# two_ant_fpga_board.net
KiCad netlist of a schematic drawn in Altium Designer
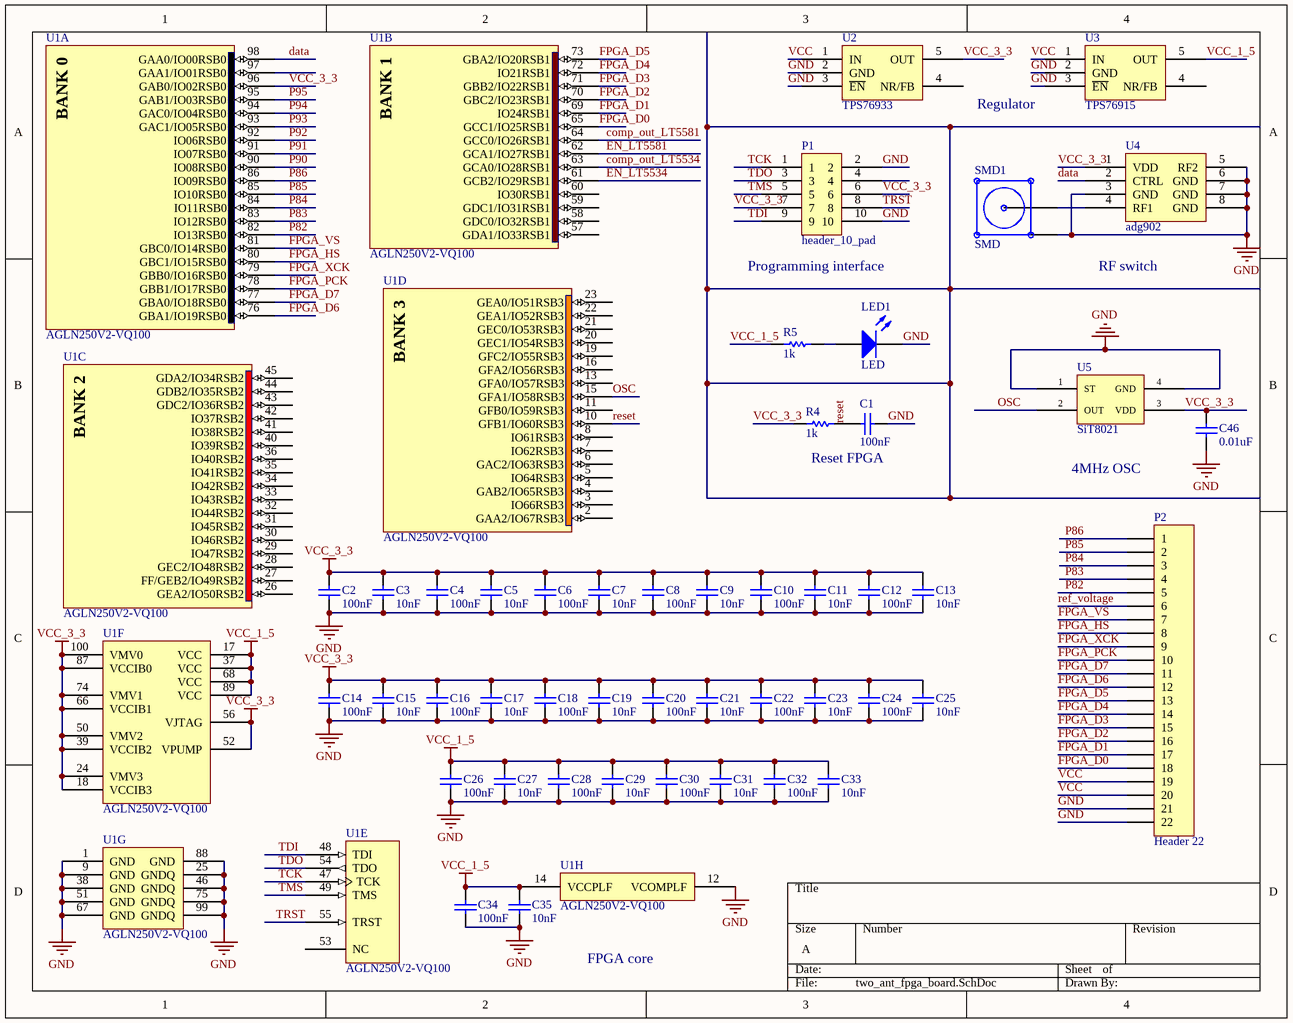
[diagram p0: two_ant_fpga_board.SchDoc]

(export (version "E")
  (design (tool "Eeschema 10.0.6"))
  (components
    (comp (ref "C1")
      (value "100nF")
      (footprint "0603")
      (description "Ceramic Capacitor (Surface Mount)")
      (fields (field (name "MANUFACTURER") "Generic Ceramic Chip Cap (TBD)") (field (name "Comment") "Cap"))
      (libsource (lib "wisp") (part "Cap"))
    )
    (comp (ref "C2")
      (value "100nF")
      (footprint "0603")
      (description "Ceramic Capacitor (Surface Mount)")
      (fields (field (name "MANUFACTURER") "Generic Ceramic Chip Cap (TBD)") (field (name "Comment") "Cap"))
      (libsource (lib "wisp") (part "Cap"))
    )
    (comp (ref "C3")
      (value "10nF")
      (footprint "0603")
      (description "Ceramic Capacitor (Surface Mount)")
      (fields (field (name "MANUFACTURER") "Generic Ceramic Chip Cap (TBD)") (field (name "Comment") "Cap"))
      (libsource (lib "wisp") (part "Cap"))
    )
    (comp (ref "C4")
      (value "100nF")
      (footprint "0603")
      (description "Ceramic Capacitor (Surface Mount)")
      (fields (field (name "MANUFACTURER") "Generic Ceramic Chip Cap (TBD)") (field (name "Comment") "Cap"))
      (libsource (lib "wisp") (part "Cap"))
    )
    (comp (ref "C5")
      (value "10nF")
      (footprint "0603")
      (description "Ceramic Capacitor (Surface Mount)")
      (fields (field (name "MANUFACTURER") "Generic Ceramic Chip Cap (TBD)") (field (name "Comment") "Cap"))
      (libsource (lib "wisp") (part "Cap"))
    )
    (comp (ref "C6")
      (value "100nF")
      (footprint "0603")
      (description "Ceramic Capacitor (Surface Mount)")
      (fields (field (name "MANUFACTURER") "Generic Ceramic Chip Cap (TBD)") (field (name "Comment") "Cap"))
      (libsource (lib "wisp") (part "Cap"))
    )
    (comp (ref "C7")
      (value "10nF")
      (footprint "0603")
      (description "Ceramic Capacitor (Surface Mount)")
      (fields (field (name "MANUFACTURER") "Generic Ceramic Chip Cap (TBD)") (field (name "Comment") "Cap"))
      (libsource (lib "wisp") (part "Cap"))
    )
    (comp (ref "C8")
      (value "100nF")
      (footprint "0603")
      (description "Ceramic Capacitor (Surface Mount)")
      (fields (field (name "MANUFACTURER") "Generic Ceramic Chip Cap (TBD)") (field (name "Comment") "Cap"))
      (libsource (lib "wisp") (part "Cap"))
    )
    (comp (ref "C9")
      (value "10nF")
      (footprint "0603")
      (description "Ceramic Capacitor (Surface Mount)")
      (fields (field (name "MANUFACTURER") "Generic Ceramic Chip Cap (TBD)") (field (name "Comment") "Cap"))
      (libsource (lib "wisp") (part "Cap"))
    )
    (comp (ref "C10")
      (value "100nF")
      (footprint "0603")
      (description "Ceramic Capacitor (Surface Mount)")
      (fields (field (name "MANUFACTURER") "Generic Ceramic Chip Cap (TBD)") (field (name "Comment") "Cap"))
      (libsource (lib "wisp") (part "Cap"))
    )
    (comp (ref "C11")
      (value "10nF")
      (footprint "0603")
      (description "Ceramic Capacitor (Surface Mount)")
      (fields (field (name "MANUFACTURER") "Generic Ceramic Chip Cap (TBD)") (field (name "Comment") "Cap"))
      (libsource (lib "wisp") (part "Cap"))
    )
    (comp (ref "C12")
      (value "100nF")
      (footprint "0603")
      (description "Ceramic Capacitor (Surface Mount)")
      (fields (field (name "MANUFACTURER") "Generic Ceramic Chip Cap (TBD)") (field (name "Comment") "Cap"))
      (libsource (lib "wisp") (part "Cap"))
    )
    (comp (ref "C13")
      (value "10nF")
      (footprint "0603")
      (description "Ceramic Capacitor (Surface Mount)")
      (fields (field (name "MANUFACTURER") "Generic Ceramic Chip Cap (TBD)") (field (name "Comment") "Cap"))
      (libsource (lib "wisp") (part "Cap"))
    )
    (comp (ref "C14")
      (value "100nF")
      (footprint "0603")
      (description "Ceramic Capacitor (Surface Mount)")
      (fields (field (name "MANUFACTURER") "Generic Ceramic Chip Cap (TBD)") (field (name "Comment") "Cap"))
      (libsource (lib "wisp") (part "Cap"))
    )
    (comp (ref "C15")
      (value "10nF")
      (footprint "0603")
      (description "Ceramic Capacitor (Surface Mount)")
      (fields (field (name "MANUFACTURER") "Generic Ceramic Chip Cap (TBD)") (field (name "Comment") "Cap"))
      (libsource (lib "wisp") (part "Cap"))
    )
    (comp (ref "C16")
      (value "100nF")
      (footprint "0603")
      (description "Ceramic Capacitor (Surface Mount)")
      (fields (field (name "MANUFACTURER") "Generic Ceramic Chip Cap (TBD)") (field (name "Comment") "Cap"))
      (libsource (lib "wisp") (part "Cap"))
    )
    (comp (ref "C17")
      (value "10nF")
      (footprint "0603")
      (description "Ceramic Capacitor (Surface Mount)")
      (fields (field (name "MANUFACTURER") "Generic Ceramic Chip Cap (TBD)") (field (name "Comment") "Cap"))
      (libsource (lib "wisp") (part "Cap"))
    )
    (comp (ref "C18")
      (value "100nF")
      (footprint "0603")
      (description "Ceramic Capacitor (Surface Mount)")
      (fields (field (name "MANUFACTURER") "Generic Ceramic Chip Cap (TBD)") (field (name "Comment") "Cap"))
      (libsource (lib "wisp") (part "Cap"))
    )
    (comp (ref "C19")
      (value "10nF")
      (footprint "0603")
      (description "Ceramic Capacitor (Surface Mount)")
      (fields (field (name "MANUFACTURER") "Generic Ceramic Chip Cap (TBD)") (field (name "Comment") "Cap"))
      (libsource (lib "wisp") (part "Cap"))
    )
    (comp (ref "C20")
      (value "100nF")
      (footprint "0603")
      (description "Ceramic Capacitor (Surface Mount)")
      (fields (field (name "MANUFACTURER") "Generic Ceramic Chip Cap (TBD)") (field (name "Comment") "Cap"))
      (libsource (lib "wisp") (part "Cap"))
    )
    (comp (ref "C21")
      (value "10nF")
      (footprint "0603")
      (description "Ceramic Capacitor (Surface Mount)")
      (fields (field (name "MANUFACTURER") "Generic Ceramic Chip Cap (TBD)") (field (name "Comment") "Cap"))
      (libsource (lib "wisp") (part "Cap"))
    )
    (comp (ref "C22")
      (value "100nF")
      (footprint "0603")
      (description "Ceramic Capacitor (Surface Mount)")
      (fields (field (name "MANUFACTURER") "Generic Ceramic Chip Cap (TBD)") (field (name "Comment") "Cap"))
      (libsource (lib "wisp") (part "Cap"))
    )
    (comp (ref "C23")
      (value "10nF")
      (footprint "0603")
      (description "Ceramic Capacitor (Surface Mount)")
      (fields (field (name "MANUFACTURER") "Generic Ceramic Chip Cap (TBD)") (field (name "Comment") "Cap"))
      (libsource (lib "wisp") (part "Cap"))
    )
    (comp (ref "C24")
      (value "100nF")
      (footprint "0603")
      (description "Ceramic Capacitor (Surface Mount)")
      (fields (field (name "MANUFACTURER") "Generic Ceramic Chip Cap (TBD)") (field (name "Comment") "Cap"))
      (libsource (lib "wisp") (part "Cap"))
    )
    (comp (ref "C25")
      (value "10nF")
      (footprint "0603")
      (description "Ceramic Capacitor (Surface Mount)")
      (fields (field (name "MANUFACTURER") "Generic Ceramic Chip Cap (TBD)") (field (name "Comment") "Cap"))
      (libsource (lib "wisp") (part "Cap"))
    )
    (comp (ref "C26")
      (value "100nF")
      (footprint "0603")
      (description "Ceramic Capacitor (Surface Mount)")
      (fields (field (name "MANUFACTURER") "Generic Ceramic Chip Cap (TBD)") (field (name "Comment") "Cap"))
      (libsource (lib "wisp") (part "Cap"))
    )
    (comp (ref "C27")
      (value "10nF")
      (footprint "0603")
      (description "Ceramic Capacitor (Surface Mount)")
      (fields (field (name "MANUFACTURER") "Generic Ceramic Chip Cap (TBD)") (field (name "Comment") "Cap"))
      (libsource (lib "wisp") (part "Cap"))
    )
    (comp (ref "C28")
      (value "100nF")
      (footprint "0603")
      (description "Ceramic Capacitor (Surface Mount)")
      (fields (field (name "MANUFACTURER") "Generic Ceramic Chip Cap (TBD)") (field (name "Comment") "Cap"))
      (libsource (lib "wisp") (part "Cap"))
    )
    (comp (ref "C29")
      (value "10nF")
      (footprint "0603")
      (description "Ceramic Capacitor (Surface Mount)")
      (fields (field (name "MANUFACTURER") "Generic Ceramic Chip Cap (TBD)") (field (name "Comment") "Cap"))
      (libsource (lib "wisp") (part "Cap"))
    )
    (comp (ref "C30")
      (value "100nF")
      (footprint "0603")
      (description "Ceramic Capacitor (Surface Mount)")
      (fields (field (name "MANUFACTURER") "Generic Ceramic Chip Cap (TBD)") (field (name "Comment") "Cap"))
      (libsource (lib "wisp") (part "Cap"))
    )
    (comp (ref "C31")
      (value "10nF")
      (footprint "0603")
      (description "Ceramic Capacitor (Surface Mount)")
      (fields (field (name "MANUFACTURER") "Generic Ceramic Chip Cap (TBD)") (field (name "Comment") "Cap"))
      (libsource (lib "wisp") (part "Cap"))
    )
    (comp (ref "C32")
      (value "100nF")
      (footprint "0603")
      (description "Ceramic Capacitor (Surface Mount)")
      (fields (field (name "MANUFACTURER") "Generic Ceramic Chip Cap (TBD)") (field (name "Comment") "Cap"))
      (libsource (lib "wisp") (part "Cap"))
    )
    (comp (ref "C33")
      (value "10nF")
      (footprint "0603")
      (description "Ceramic Capacitor (Surface Mount)")
      (fields (field (name "MANUFACTURER") "Generic Ceramic Chip Cap (TBD)") (field (name "Comment") "Cap"))
      (libsource (lib "wisp") (part "Cap"))
    )
    (comp (ref "C34")
      (value "100nF")
      (footprint "0603")
      (description "Ceramic Capacitor (Surface Mount)")
      (fields (field (name "MANUFACTURER") "Generic Ceramic Chip Cap (TBD)") (field (name "Comment") "Cap"))
      (libsource (lib "wisp") (part "Cap"))
    )
    (comp (ref "C35")
      (value "10nF")
      (footprint "0603")
      (description "Ceramic Capacitor (Surface Mount)")
      (fields (field (name "MANUFACTURER") "Generic Ceramic Chip Cap (TBD)") (field (name "Comment") "Cap"))
      (libsource (lib "wisp") (part "Cap"))
    )
    (comp (ref "C46")
      (value "0.01uF")
      (footprint "0603")
      (description "Ceramic Capacitor (Surface Mount)")
      (fields (field (name "MANUFACTURER") "Generic Ceramic Chip Cap (TBD)") (field (name "Comment") "Cap"))
      (libsource (lib "wisp") (part "Cap"))
    )
    (comp (ref "LED1") (value "LED") (libsource (lib "pengyulib") (part "LED")))
    (comp (ref "P1")
      (value "header_10_pad")
      (footprint "header_10_pad")
      (libsource (lib "pengyulib") (part "header_10_pad"))
    )
    (comp (ref "P2")
      (value "Header 22")
      (footprint "HDR1X22")
      (description "Header, 22-Pin")
      (fields (field (name "PUBLISHER") "Altium Limited"))
      (libsource (lib "Miscellaneous Connectors") (part "Header 22"))
    )
    (comp (ref "R4")
      (value "1k")
      (footprint "0603")
      (description "Chip Resistor (Surface Mount)")
      (fields (field (name "MANUFACTURER") "Generic Chip Res (TBD)") (field (name "Comment") "Res"))
      (libsource (lib "wisp") (part "Res"))
    )
    (comp (ref "R5")
      (value "1k")
      (footprint "0603")
      (description "Chip Resistor (Surface Mount)")
      (fields (field (name "MANUFACTURER") "Generic Chip Res (TBD)") (field (name "Comment") "Res"))
      (libsource (lib "wisp") (part "Res"))
    )
    (comp (ref "SMD1") (value "SMD") (footprint "SMD") (libsource (lib "pengyulib") (part "SMD")))
    (comp (ref "U1")
      (value "AGLN250V2-VQ100")
      (footprint "VQ100_N")
      (fields (field (name "PUBLISHER") "Altium Limited"))
      (libsource (lib "Actel IGLOO nano") (part "AGLN250V2-VQ100"))
    )
    (comp (ref "U2")
      (value "TPS76933")
      (footprint "TPS73633")
      (description "TPS73633")
      (libsource (lib "pengyulib") (part "TPS76933"))
    )
    (comp (ref "U3")
      (value "TPS76915")
      (footprint "TPS73633")
      (description "TPS73633")
      (libsource (lib "pengyulib") (part "TPS76915"))
    )
    (comp (ref "U4") (value "adg902") (footprint "ADG902") (libsource (lib "pengyulib") (part "adg902")))
    (comp (ref "U5") (value "SiT8021") (footprint "SiT8021") (libsource (lib "pengyulib") (part "SiT8021")))
  )
  (nets
    (net (code "1") (name "/EN_LT5534") (class "Default")
      (node (ref "U1") (pin "61") (pinfunction "GCB2/IO29RSB1_61") (pintype "bidirectional"))
    )
    (net (code "2") (name "/EN_LT5581") (class "Default")
      (node (ref "U1") (pin "62") (pinfunction "GCA1/IO27RSB1_62") (pintype "bidirectional"))
    )
    (net (code "3") (name "/FPGA_D0") (class "Default")
      (node (ref "P2") (pin "18") (pinfunction "18_18") (pintype "passive"))
      (node (ref "U1") (pin "65") (pinfunction "GCC1/IO25RSB1_65") (pintype "bidirectional"))
    )
    (net (code "4") (name "/FPGA_D1") (class "Default")
      (node (ref "P2") (pin "17") (pinfunction "17_17") (pintype "passive"))
      (node (ref "U1") (pin "69") (pinfunction "IO24RSB1_69") (pintype "bidirectional"))
    )
    (net (code "5") (name "/FPGA_D2") (class "Default")
      (node (ref "P2") (pin "16") (pinfunction "16_16") (pintype "passive"))
      (node (ref "U1") (pin "70") (pinfunction "GBC2/IO23RSB1_70") (pintype "bidirectional"))
    )
    (net (code "6") (name "/FPGA_D3") (class "Default")
      (node (ref "P2") (pin "15") (pinfunction "15_15") (pintype "passive"))
      (node (ref "U1") (pin "71") (pinfunction "GBB2/IO22RSB1_71") (pintype "bidirectional"))
    )
    (net (code "7") (name "/FPGA_D4") (class "Default")
      (node (ref "P2") (pin "14") (pinfunction "14_14") (pintype "passive"))
      (node (ref "U1") (pin "72") (pinfunction "IO21RSB1_72") (pintype "bidirectional"))
    )
    (net (code "8") (name "/FPGA_D5") (class "Default")
      (node (ref "P2") (pin "13") (pinfunction "13_13") (pintype "passive"))
      (node (ref "U1") (pin "73") (pinfunction "GBA2/IO20RSB1_73") (pintype "bidirectional"))
    )
    (net (code "9") (name "/FPGA_D6") (class "Default")
      (node (ref "P2") (pin "12") (pinfunction "12_12") (pintype "passive"))
      (node (ref "U1") (pin "76") (pinfunction "GBA1/IO19RSB0_76") (pintype "bidirectional"))
    )
    (net (code "10") (name "/FPGA_D7") (class "Default")
      (node (ref "P2") (pin "11") (pinfunction "11_11") (pintype "passive"))
      (node (ref "U1") (pin "77") (pinfunction "GBA0/IO18RSB0_77") (pintype "bidirectional"))
    )
    (net (code "11") (name "/FPGA_HS") (class "Default")
      (node (ref "P2") (pin "8") (pinfunction "8_8") (pintype "passive"))
      (node (ref "U1") (pin "80") (pinfunction "GBC1/IO15RSB0_80") (pintype "bidirectional"))
    )
    (net (code "12") (name "/FPGA_PCK") (class "Default")
      (node (ref "P2") (pin "10") (pinfunction "10_10") (pintype "passive"))
      (node (ref "U1") (pin "78") (pinfunction "GBB1/IO17RSB0_78") (pintype "bidirectional"))
    )
    (net (code "13") (name "/FPGA_VS") (class "Default")
      (node (ref "P2") (pin "7") (pinfunction "7_7") (pintype "passive"))
      (node (ref "U1") (pin "81") (pinfunction "GBC0/IO14RSB0_81") (pintype "bidirectional"))
    )
    (net (code "14") (name "/FPGA_XCK") (class "Default")
      (node (ref "P2") (pin "9") (pinfunction "9_9") (pintype "passive"))
      (node (ref "U1") (pin "79") (pinfunction "GBB0/IO16RSB0_79") (pintype "bidirectional"))
    )
    (net (code "15") (name "/OSC") (class "Default")
      (node (ref "U1") (pin "15") (pinfunction "GFA1/IO58RSB3_15") (pintype "bidirectional"))
      (node (ref "U5") (pin "2") (pinfunction "OUT_2") (pintype "passive"))
    )
    (net (code "16") (name "/P82") (class "Default")
      (node (ref "P2") (pin "5") (pinfunction "5_5") (pintype "passive"))
      (node (ref "U1") (pin "82") (pinfunction "IO13RSB0_82") (pintype "bidirectional"))
    )
    (net (code "17") (name "/P83") (class "Default")
      (node (ref "P2") (pin "4") (pinfunction "4_4") (pintype "passive"))
      (node (ref "U1") (pin "83") (pinfunction "IO12RSB0_83") (pintype "bidirectional"))
    )
    (net (code "18") (name "/P84") (class "Default")
      (node (ref "P2") (pin "3") (pinfunction "3_3") (pintype "passive"))
      (node (ref "U1") (pin "84") (pinfunction "IO11RSB0_84") (pintype "bidirectional"))
    )
    (net (code "19") (name "/P85") (class "Default")
      (node (ref "P2") (pin "2") (pinfunction "2_2") (pintype "passive"))
      (node (ref "U1") (pin "85") (pinfunction "IO10RSB0_85") (pintype "bidirectional"))
    )
    (net (code "20") (name "/P86") (class "Default")
      (node (ref "P2") (pin "1") (pinfunction "1_1") (pintype "passive"))
      (node (ref "U1") (pin "86") (pinfunction "IO09RSB0_86") (pintype "bidirectional"))
    )
    (net (code "21") (name "/P90") (class "Default")
      (node (ref "U1") (pin "90") (pinfunction "IO08RSB0_90") (pintype "bidirectional"))
    )
    (net (code "22") (name "/P91") (class "Default")
      (node (ref "U1") (pin "91") (pinfunction "IO07RSB0_91") (pintype "bidirectional"))
    )
    (net (code "23") (name "/P92") (class "Default")
      (node (ref "U1") (pin "92") (pinfunction "IO06RSB0_92") (pintype "bidirectional"))
    )
    (net (code "24") (name "/P93") (class "Default")
      (node (ref "U1") (pin "93") (pinfunction "GAC1/IO05RSB0_93") (pintype "bidirectional"))
    )
    (net (code "25") (name "/P94") (class "Default")
      (node (ref "U1") (pin "94") (pinfunction "GAC0/IO04RSB0_94") (pintype "bidirectional"))
    )
    (net (code "26") (name "/P95") (class "Default")
      (node (ref "U1") (pin "95") (pinfunction "GAB1/IO03RSB0_95") (pintype "bidirectional"))
    )
    (net (code "27") (name "/TCK") (class "Default")
      (node (ref "P1") (pin "1") (pinfunction "1_1") (pintype "passive"))
      (node (ref "U1") (pin "47") (pinfunction "TCK_47") (pintype "input"))
    )
    (net (code "28") (name "/TDI") (class "Default")
      (node (ref "P1") (pin "9") (pinfunction "9_9") (pintype "passive"))
      (node (ref "U1") (pin "48") (pinfunction "TDI_48") (pintype "input"))
    )
    (net (code "29") (name "/TDO") (class "Default")
      (node (ref "P1") (pin "3") (pinfunction "3_3") (pintype "passive"))
      (node (ref "U1") (pin "54") (pinfunction "TDO_54") (pintype "output"))
    )
    (net (code "30") (name "/TMS") (class "Default")
      (node (ref "P1") (pin "5") (pinfunction "5_5") (pintype "passive"))
      (node (ref "U1") (pin "49") (pinfunction "TMS_49") (pintype "input"))
    )
    (net (code "31") (name "/TRST") (class "Default")
      (node (ref "P1") (pin "8") (pinfunction "8_8") (pintype "passive"))
      (node (ref "U1") (pin "55") (pinfunction "TRST_55") (pintype "input"))
    )
    (net (code "32") (name "/VCC") (class "Default")
      (node (ref "P2") (pin "19") (pinfunction "19_19") (pintype "passive"))
      (node (ref "P2") (pin "20") (pinfunction "20_20") (pintype "passive"))
      (node (ref "U2") (pin "1") (pinfunction "IN_1") (pintype "passive"))
      (node (ref "U3") (pin "1") (pinfunction "IN_1") (pintype "passive"))
    )
    (net (code "33") (name "/comp_out_LT5534") (class "Default")
      (node (ref "U1") (pin "63") (pinfunction "GCA0/IO28RSB1_63") (pintype "bidirectional"))
    )
    (net (code "34") (name "/comp_out_LT5581") (class "Default")
      (node (ref "U1") (pin "64") (pinfunction "GCC0/IO26RSB1_64") (pintype "bidirectional"))
    )
    (net (code "35") (name "/data") (class "Default")
      (node (ref "U1") (pin "98") (pinfunction "GAA0/IO00RSB0_98") (pintype "bidirectional"))
      (node (ref "U4") (pin "2") (pinfunction "CTRL_2") (pintype "passive"))
    )
    (net (code "36") (name "/ref_voltage") (class "Default")
      (node (ref "P2") (pin "6") (pinfunction "6_6") (pintype "passive"))
    )
    (net (code "37") (name "/reset") (class "Default")
      (node (ref "C1") (pin "2") (pinfunction "2_2") (pintype "passive"))
      (node (ref "R4") (pin "1") (pinfunction "1_1") (pintype "passive"))
      (node (ref "U1") (pin "10") (pinfunction "GFB1/IO60RSB3_10") (pintype "bidirectional"))
    )
    (net (code "38") (name "GND") (class "Default")
      (node (ref "C1") (pin "1") (pinfunction "1_1") (pintype "passive"))
      (node (ref "C10") (pin "1") (pinfunction "1_1") (pintype "passive"))
      (node (ref "C11") (pin "1") (pinfunction "1_1") (pintype "passive"))
      (node (ref "C12") (pin "1") (pinfunction "1_1") (pintype "passive"))
      (node (ref "C13") (pin "1") (pinfunction "1_1") (pintype "passive"))
      (node (ref "C14") (pin "1") (pinfunction "1_1") (pintype "passive"))
      (node (ref "C15") (pin "1") (pinfunction "1_1") (pintype "passive"))
      (node (ref "C16") (pin "1") (pinfunction "1_1") (pintype "passive"))
      (node (ref "C17") (pin "1") (pinfunction "1_1") (pintype "passive"))
      (node (ref "C18") (pin "1") (pinfunction "1_1") (pintype "passive"))
      (node (ref "C19") (pin "1") (pinfunction "1_1") (pintype "passive"))
      (node (ref "C2") (pin "1") (pinfunction "1_1") (pintype "passive"))
      (node (ref "C20") (pin "1") (pinfunction "1_1") (pintype "passive"))
      (node (ref "C21") (pin "1") (pinfunction "1_1") (pintype "passive"))
      (node (ref "C22") (pin "1") (pinfunction "1_1") (pintype "passive"))
      (node (ref "C23") (pin "1") (pinfunction "1_1") (pintype "passive"))
      (node (ref "C24") (pin "1") (pinfunction "1_1") (pintype "passive"))
      (node (ref "C25") (pin "1") (pinfunction "1_1") (pintype "passive"))
      (node (ref "C26") (pin "1") (pinfunction "1_1") (pintype "passive"))
      (node (ref "C27") (pin "1") (pinfunction "1_1") (pintype "passive"))
      (node (ref "C28") (pin "1") (pinfunction "1_1") (pintype "passive"))
      (node (ref "C29") (pin "1") (pinfunction "1_1") (pintype "passive"))
      (node (ref "C3") (pin "1") (pinfunction "1_1") (pintype "passive"))
      (node (ref "C30") (pin "1") (pinfunction "1_1") (pintype "passive"))
      (node (ref "C31") (pin "1") (pinfunction "1_1") (pintype "passive"))
      (node (ref "C32") (pin "1") (pinfunction "1_1") (pintype "passive"))
      (node (ref "C33") (pin "1") (pinfunction "1_1") (pintype "passive"))
      (node (ref "C34") (pin "1") (pinfunction "1_1") (pintype "passive"))
      (node (ref "C35") (pin "1") (pinfunction "1_1") (pintype "passive"))
      (node (ref "C4") (pin "1") (pinfunction "1_1") (pintype "passive"))
      (node (ref "C46") (pin "1") (pinfunction "1_1") (pintype "passive"))
      (node (ref "C5") (pin "1") (pinfunction "1_1") (pintype "passive"))
      (node (ref "C6") (pin "1") (pinfunction "1_1") (pintype "passive"))
      (node (ref "C7") (pin "1") (pinfunction "1_1") (pintype "passive"))
      (node (ref "C8") (pin "1") (pinfunction "1_1") (pintype "passive"))
      (node (ref "C9") (pin "1") (pinfunction "1_1") (pintype "passive"))
      (node (ref "LED1") (pin "2") (pinfunction "K_2") (pintype "passive"))
      (node (ref "P1") (pin "10") (pinfunction "10_10") (pintype "passive"))
      (node (ref "P1") (pin "2") (pinfunction "2_2") (pintype "passive"))
      (node (ref "P2") (pin "21") (pinfunction "21_21") (pintype "passive"))
      (node (ref "P2") (pin "22") (pinfunction "22_22") (pintype "passive"))
      (node (ref "SMD1") (pin "1") (pinfunction "1_1") (pintype "passive"))
      (node (ref "U1") (pin "1") (pinfunction "GND_1") (pintype "power_in"))
      (node (ref "U1") (pin "12") (pinfunction "VCOMPLF_12") (pintype "power_in"))
      (node (ref "U1") (pin "25") (pinfunction "GNDQ_25") (pintype "power_in"))
      (node (ref "U1") (pin "38") (pinfunction "GND_38") (pintype "power_in"))
      (node (ref "U1") (pin "46") (pinfunction "GNDQ_46") (pintype "power_in"))
      (node (ref "U1") (pin "51") (pinfunction "GND_51") (pintype "power_in"))
      (node (ref "U1") (pin "67") (pinfunction "GND_67") (pintype "power_in"))
      (node (ref "U1") (pin "75") (pinfunction "GNDQ_75") (pintype "power_in"))
      (node (ref "U1") (pin "88") (pinfunction "GND_88") (pintype "power_in"))
      (node (ref "U1") (pin "9") (pinfunction "GND_9") (pintype "power_in"))
      (node (ref "U1") (pin "99") (pinfunction "GNDQ_99") (pintype "power_in"))
      (node (ref "U2") (pin "2") (pinfunction "GND_2") (pintype "passive"))
      (node (ref "U2") (pin "3") (pinfunction "~{EN}_3") (pintype "passive"))
      (node (ref "U3") (pin "2") (pinfunction "GND_2") (pintype "passive"))
      (node (ref "U3") (pin "3") (pinfunction "~{EN}_3") (pintype "passive"))
      (node (ref "U4") (pin "3") (pinfunction "GND_3") (pintype "passive"))
      (node (ref "U4") (pin "5") (pinfunction "RF2_5") (pintype "passive"))
      (node (ref "U4") (pin "6") (pinfunction "GND_6") (pintype "passive"))
      (node (ref "U4") (pin "7") (pinfunction "GND_7") (pintype "passive"))
      (node (ref "U4") (pin "8") (pinfunction "GND_8") (pintype "passive"))
      (node (ref "U5") (pin "1") (pinfunction "ST_1") (pintype "passive"))
      (node (ref "U5") (pin "4") (pinfunction "GND_4") (pintype "passive"))
    )
    (net (code "39") (name "Net-(LED1-A)") (class "Default")
      (node (ref "LED1") (pin "1") (pinfunction "A_1") (pintype "passive"))
      (node (ref "R5") (pin "1") (pinfunction "1_1") (pintype "passive"))
    )
    (net (code "40") (name "Net-(U4-RF1)") (class "Default")
      (node (ref "SMD1") (pin "2") (pinfunction "2_2") (pintype "passive"))
      (node (ref "U4") (pin "4") (pinfunction "RF1_4") (pintype "passive"))
    )
    (net (code "41") (name "VCC_1_5") (class "Default")
      (node (ref "C26") (pin "2") (pinfunction "2_2") (pintype "passive"))
      (node (ref "C27") (pin "2") (pinfunction "2_2") (pintype "passive"))
      (node (ref "C28") (pin "2") (pinfunction "2_2") (pintype "passive"))
      (node (ref "C29") (pin "2") (pinfunction "2_2") (pintype "passive"))
      (node (ref "C30") (pin "2") (pinfunction "2_2") (pintype "passive"))
      (node (ref "C31") (pin "2") (pinfunction "2_2") (pintype "passive"))
      (node (ref "C32") (pin "2") (pinfunction "2_2") (pintype "passive"))
      (node (ref "C33") (pin "2") (pinfunction "2_2") (pintype "passive"))
      (node (ref "C34") (pin "2") (pinfunction "2_2") (pintype "passive"))
      (node (ref "C35") (pin "2") (pinfunction "2_2") (pintype "passive"))
      (node (ref "R5") (pin "2") (pinfunction "2_2") (pintype "passive"))
      (node (ref "U1") (pin "14") (pinfunction "VCCPLF_14") (pintype "power_in"))
      (node (ref "U1") (pin "17") (pinfunction "VCC_17") (pintype "power_in"))
      (node (ref "U1") (pin "37") (pinfunction "VCC_37") (pintype "power_in"))
      (node (ref "U1") (pin "68") (pinfunction "VCC_68") (pintype "power_in"))
      (node (ref "U1") (pin "89") (pinfunction "VCC_89") (pintype "power_in"))
      (node (ref "U3") (pin "5") (pinfunction "OUT_5") (pintype "passive"))
    )
    (net (code "42") (name "VCC_3_3") (class "Default")
      (node (ref "C10") (pin "2") (pinfunction "2_2") (pintype "passive"))
      (node (ref "C11") (pin "2") (pinfunction "2_2") (pintype "passive"))
      (node (ref "C12") (pin "2") (pinfunction "2_2") (pintype "passive"))
      (node (ref "C13") (pin "2") (pinfunction "2_2") (pintype "passive"))
      (node (ref "C14") (pin "2") (pinfunction "2_2") (pintype "passive"))
      (node (ref "C15") (pin "2") (pinfunction "2_2") (pintype "passive"))
      (node (ref "C16") (pin "2") (pinfunction "2_2") (pintype "passive"))
      (node (ref "C17") (pin "2") (pinfunction "2_2") (pintype "passive"))
      (node (ref "C18") (pin "2") (pinfunction "2_2") (pintype "passive"))
      (node (ref "C19") (pin "2") (pinfunction "2_2") (pintype "passive"))
      (node (ref "C2") (pin "2") (pinfunction "2_2") (pintype "passive"))
      (node (ref "C20") (pin "2") (pinfunction "2_2") (pintype "passive"))
      (node (ref "C21") (pin "2") (pinfunction "2_2") (pintype "passive"))
      (node (ref "C22") (pin "2") (pinfunction "2_2") (pintype "passive"))
      (node (ref "C23") (pin "2") (pinfunction "2_2") (pintype "passive"))
      (node (ref "C24") (pin "2") (pinfunction "2_2") (pintype "passive"))
      (node (ref "C25") (pin "2") (pinfunction "2_2") (pintype "passive"))
      (node (ref "C3") (pin "2") (pinfunction "2_2") (pintype "passive"))
      (node (ref "C4") (pin "2") (pinfunction "2_2") (pintype "passive"))
      (node (ref "C46") (pin "2") (pinfunction "2_2") (pintype "passive"))
      (node (ref "C5") (pin "2") (pinfunction "2_2") (pintype "passive"))
      (node (ref "C6") (pin "2") (pinfunction "2_2") (pintype "passive"))
      (node (ref "C7") (pin "2") (pinfunction "2_2") (pintype "passive"))
      (node (ref "C8") (pin "2") (pinfunction "2_2") (pintype "passive"))
      (node (ref "C9") (pin "2") (pinfunction "2_2") (pintype "passive"))
      (node (ref "P1") (pin "6") (pinfunction "6_6") (pintype "passive"))
      (node (ref "P1") (pin "7") (pinfunction "7_7") (pintype "passive"))
      (node (ref "R4") (pin "2") (pinfunction "2_2") (pintype "passive"))
      (node (ref "U1") (pin "100") (pinfunction "VMV0_100") (pintype "power_in"))
      (node (ref "U1") (pin "18") (pinfunction "VCCIB3_18") (pintype "power_in"))
      (node (ref "U1") (pin "24") (pinfunction "VMV3_24") (pintype "power_in"))
      (node (ref "U1") (pin "39") (pinfunction "VCCIB2_39") (pintype "power_in"))
      (node (ref "U1") (pin "50") (pinfunction "VMV2_50") (pintype "power_in"))
      (node (ref "U1") (pin "52") (pinfunction "VPUMP_52") (pintype "power_in"))
      (node (ref "U1") (pin "56") (pinfunction "VJTAG_56") (pintype "power_in"))
      (node (ref "U1") (pin "66") (pinfunction "VCCIB1_66") (pintype "power_in"))
      (node (ref "U1") (pin "74") (pinfunction "VMV1_74") (pintype "power_in"))
      (node (ref "U1") (pin "87") (pinfunction "VCCIB0_87") (pintype "power_in"))
      (node (ref "U1") (pin "96") (pinfunction "GAB0/IO02RSB0_96") (pintype "bidirectional"))
      (node (ref "U2") (pin "5") (pinfunction "OUT_5") (pintype "passive"))
      (node (ref "U4") (pin "1") (pinfunction "VDD_1") (pintype "passive"))
      (node (ref "U5") (pin "3") (pinfunction "VDD_3") (pintype "passive"))
    )
    (net (code "43") (name "unconnected-(P1-Pad4)") (class "Default")
      (node (ref "P1") (pin "4") (pinfunction "4_4") (pintype "passive"))
    )
    (net (code "44") (name "unconnected-(U1A-GAA1{slash}IO01RSB0-Pad97)") (class "Default")
      (node (ref "U1") (pin "97") (pinfunction "GAA1/IO01RSB0_97") (pintype "bidirectional"))
    )
    (net (code "45") (name "unconnected-(U1B-GDA1{slash}IO33RSB1-Pad57)") (class "Default")
      (node (ref "U1") (pin "57") (pinfunction "GDA1/IO33RSB1_57") (pintype "bidirectional"))
    )
    (net (code "46") (name "unconnected-(U1B-GDC0{slash}IO32RSB1-Pad58)") (class "Default")
      (node (ref "U1") (pin "58") (pinfunction "GDC0/IO32RSB1_58") (pintype "bidirectional"))
    )
    (net (code "47") (name "unconnected-(U1B-GDC1{slash}IO31RSB1-Pad59)") (class "Default")
      (node (ref "U1") (pin "59") (pinfunction "GDC1/IO31RSB1_59") (pintype "bidirectional"))
    )
    (net (code "48") (name "unconnected-(U1B-IO30RSB1-Pad60)") (class "Default")
      (node (ref "U1") (pin "60") (pinfunction "IO30RSB1_60") (pintype "bidirectional"))
    )
    (net (code "49") (name "unconnected-(U1C-FF{slash}GEB2{slash}IO49RSB2-Pad27)") (class "Default")
      (node (ref "U1") (pin "27") (pinfunction "FF/GEB2/IO49RSB2_27") (pintype "bidirectional"))
    )
    (net (code "50") (name "unconnected-(U1C-GDA2{slash}IO34RSB2-Pad45)") (class "Default")
      (node (ref "U1") (pin "45") (pinfunction "GDA2/IO34RSB2_45") (pintype "bidirectional"))
    )
    (net (code "51") (name "unconnected-(U1C-GDB2{slash}IO35RSB2-Pad44)") (class "Default")
      (node (ref "U1") (pin "44") (pinfunction "GDB2/IO35RSB2_44") (pintype "bidirectional"))
    )
    (net (code "52") (name "unconnected-(U1C-GDC2{slash}IO36RSB2-Pad43)") (class "Default")
      (node (ref "U1") (pin "43") (pinfunction "GDC2/IO36RSB2_43") (pintype "bidirectional"))
    )
    (net (code "53") (name "unconnected-(U1C-GEA2{slash}IO50RSB2-Pad26)") (class "Default")
      (node (ref "U1") (pin "26") (pinfunction "GEA2/IO50RSB2_26") (pintype "bidirectional"))
    )
    (net (code "54") (name "unconnected-(U1C-GEC2{slash}IO48RSB2-Pad28)") (class "Default")
      (node (ref "U1") (pin "28") (pinfunction "GEC2/IO48RSB2_28") (pintype "bidirectional"))
    )
    (net (code "55") (name "unconnected-(U1C-IO37RSB2-Pad42)") (class "Default")
      (node (ref "U1") (pin "42") (pinfunction "IO37RSB2_42") (pintype "bidirectional"))
    )
    (net (code "56") (name "unconnected-(U1C-IO38RSB2-Pad41)") (class "Default")
      (node (ref "U1") (pin "41") (pinfunction "IO38RSB2_41") (pintype "bidirectional"))
    )
    (net (code "57") (name "unconnected-(U1C-IO39RSB2-Pad40)") (class "Default")
      (node (ref "U1") (pin "40") (pinfunction "IO39RSB2_40") (pintype "bidirectional"))
    )
    (net (code "58") (name "unconnected-(U1C-IO40RSB2-Pad36)") (class "Default")
      (node (ref "U1") (pin "36") (pinfunction "IO40RSB2_36") (pintype "bidirectional"))
    )
    (net (code "59") (name "unconnected-(U1C-IO41RSB2-Pad35)") (class "Default")
      (node (ref "U1") (pin "35") (pinfunction "IO41RSB2_35") (pintype "bidirectional"))
    )
    (net (code "60") (name "unconnected-(U1C-IO42RSB2-Pad34)") (class "Default")
      (node (ref "U1") (pin "34") (pinfunction "IO42RSB2_34") (pintype "bidirectional"))
    )
    (net (code "61") (name "unconnected-(U1C-IO43RSB2-Pad33)") (class "Default")
      (node (ref "U1") (pin "33") (pinfunction "IO43RSB2_33") (pintype "bidirectional"))
    )
    (net (code "62") (name "unconnected-(U1C-IO44RSB2-Pad32)") (class "Default")
      (node (ref "U1") (pin "32") (pinfunction "IO44RSB2_32") (pintype "bidirectional"))
    )
    (net (code "63") (name "unconnected-(U1C-IO45RSB2-Pad31)") (class "Default")
      (node (ref "U1") (pin "31") (pinfunction "IO45RSB2_31") (pintype "bidirectional"))
    )
    (net (code "64") (name "unconnected-(U1C-IO46RSB2-Pad30)") (class "Default")
      (node (ref "U1") (pin "30") (pinfunction "IO46RSB2_30") (pintype "bidirectional"))
    )
    (net (code "65") (name "unconnected-(U1C-IO47RSB2-Pad29)") (class "Default")
      (node (ref "U1") (pin "29") (pinfunction "IO47RSB2_29") (pintype "bidirectional"))
    )
    (net (code "66") (name "unconnected-(U1D-GAA2{slash}IO67RSB3-Pad2)") (class "Default")
      (node (ref "U1") (pin "2") (pinfunction "GAA2/IO67RSB3_2") (pintype "bidirectional"))
    )
    (net (code "67") (name "unconnected-(U1D-GAB2{slash}IO65RSB3-Pad4)") (class "Default")
      (node (ref "U1") (pin "4") (pinfunction "GAB2/IO65RSB3_4") (pintype "bidirectional"))
    )
    (net (code "68") (name "unconnected-(U1D-GAC2{slash}IO63RSB3-Pad6)") (class "Default")
      (node (ref "U1") (pin "6") (pinfunction "GAC2/IO63RSB3_6") (pintype "bidirectional"))
    )
    (net (code "69") (name "unconnected-(U1D-GEA0{slash}IO51RSB3-Pad23)") (class "Default")
      (node (ref "U1") (pin "23") (pinfunction "GEA0/IO51RSB3_23") (pintype "bidirectional"))
    )
    (net (code "70") (name "unconnected-(U1D-GEA1{slash}IO52RSB3-Pad22)") (class "Default")
      (node (ref "U1") (pin "22") (pinfunction "GEA1/IO52RSB3_22") (pintype "bidirectional"))
    )
    (net (code "71") (name "unconnected-(U1D-GEC0{slash}IO53RSB3-Pad21)") (class "Default")
      (node (ref "U1") (pin "21") (pinfunction "GEC0/IO53RSB3_21") (pintype "bidirectional"))
    )
    (net (code "72") (name "unconnected-(U1D-GEC1{slash}IO54RSB3-Pad20)") (class "Default")
      (node (ref "U1") (pin "20") (pinfunction "GEC1/IO54RSB3_20") (pintype "bidirectional"))
    )
    (net (code "73") (name "unconnected-(U1D-GFA0{slash}IO57RSB3-Pad13)") (class "Default")
      (node (ref "U1") (pin "13") (pinfunction "GFA0/IO57RSB3_13") (pintype "bidirectional"))
    )
    (net (code "74") (name "unconnected-(U1D-GFA2{slash}IO56RSB3-Pad16)") (class "Default")
      (node (ref "U1") (pin "16") (pinfunction "GFA2/IO56RSB3_16") (pintype "bidirectional"))
    )
    (net (code "75") (name "unconnected-(U1D-GFB0{slash}IO59RSB3-Pad11)") (class "Default")
      (node (ref "U1") (pin "11") (pinfunction "GFB0/IO59RSB3_11") (pintype "bidirectional"))
    )
    (net (code "76") (name "unconnected-(U1D-GFC2{slash}IO55RSB3-Pad19)") (class "Default")
      (node (ref "U1") (pin "19") (pinfunction "GFC2/IO55RSB3_19") (pintype "bidirectional"))
    )
    (net (code "77") (name "unconnected-(U1D-IO61RSB3-Pad8)") (class "Default")
      (node (ref "U1") (pin "8") (pinfunction "IO61RSB3_8") (pintype "bidirectional"))
    )
    (net (code "78") (name "unconnected-(U1D-IO62RSB3-Pad7)") (class "Default")
      (node (ref "U1") (pin "7") (pinfunction "IO62RSB3_7") (pintype "bidirectional"))
    )
    (net (code "79") (name "unconnected-(U1D-IO64RSB3-Pad5)") (class "Default")
      (node (ref "U1") (pin "5") (pinfunction "IO64RSB3_5") (pintype "bidirectional"))
    )
    (net (code "80") (name "unconnected-(U1D-IO66RSB3-Pad3)") (class "Default")
      (node (ref "U1") (pin "3") (pinfunction "IO66RSB3_3") (pintype "bidirectional"))
    )
    (net (code "81") (name "unconnected-(U1E-NC-Pad53)") (class "Default")
      (node (ref "U1") (pin "53") (pinfunction "NC_53") (pintype "passive"))
    )
    (net (code "82") (name "unconnected-(U2-NR{slash}FB-Pad4)") (class "Default")
      (node (ref "U2") (pin "4") (pinfunction "NR/FB_4") (pintype "passive"))
    )
    (net (code "83") (name "unconnected-(U3-NR{slash}FB-Pad4)") (class "Default")
      (node (ref "U3") (pin "4") (pinfunction "NR/FB_4") (pintype "passive"))
    )
  )
)
